# asam1_4.net
KiCad netlist of a schematic drawn in EAGLE
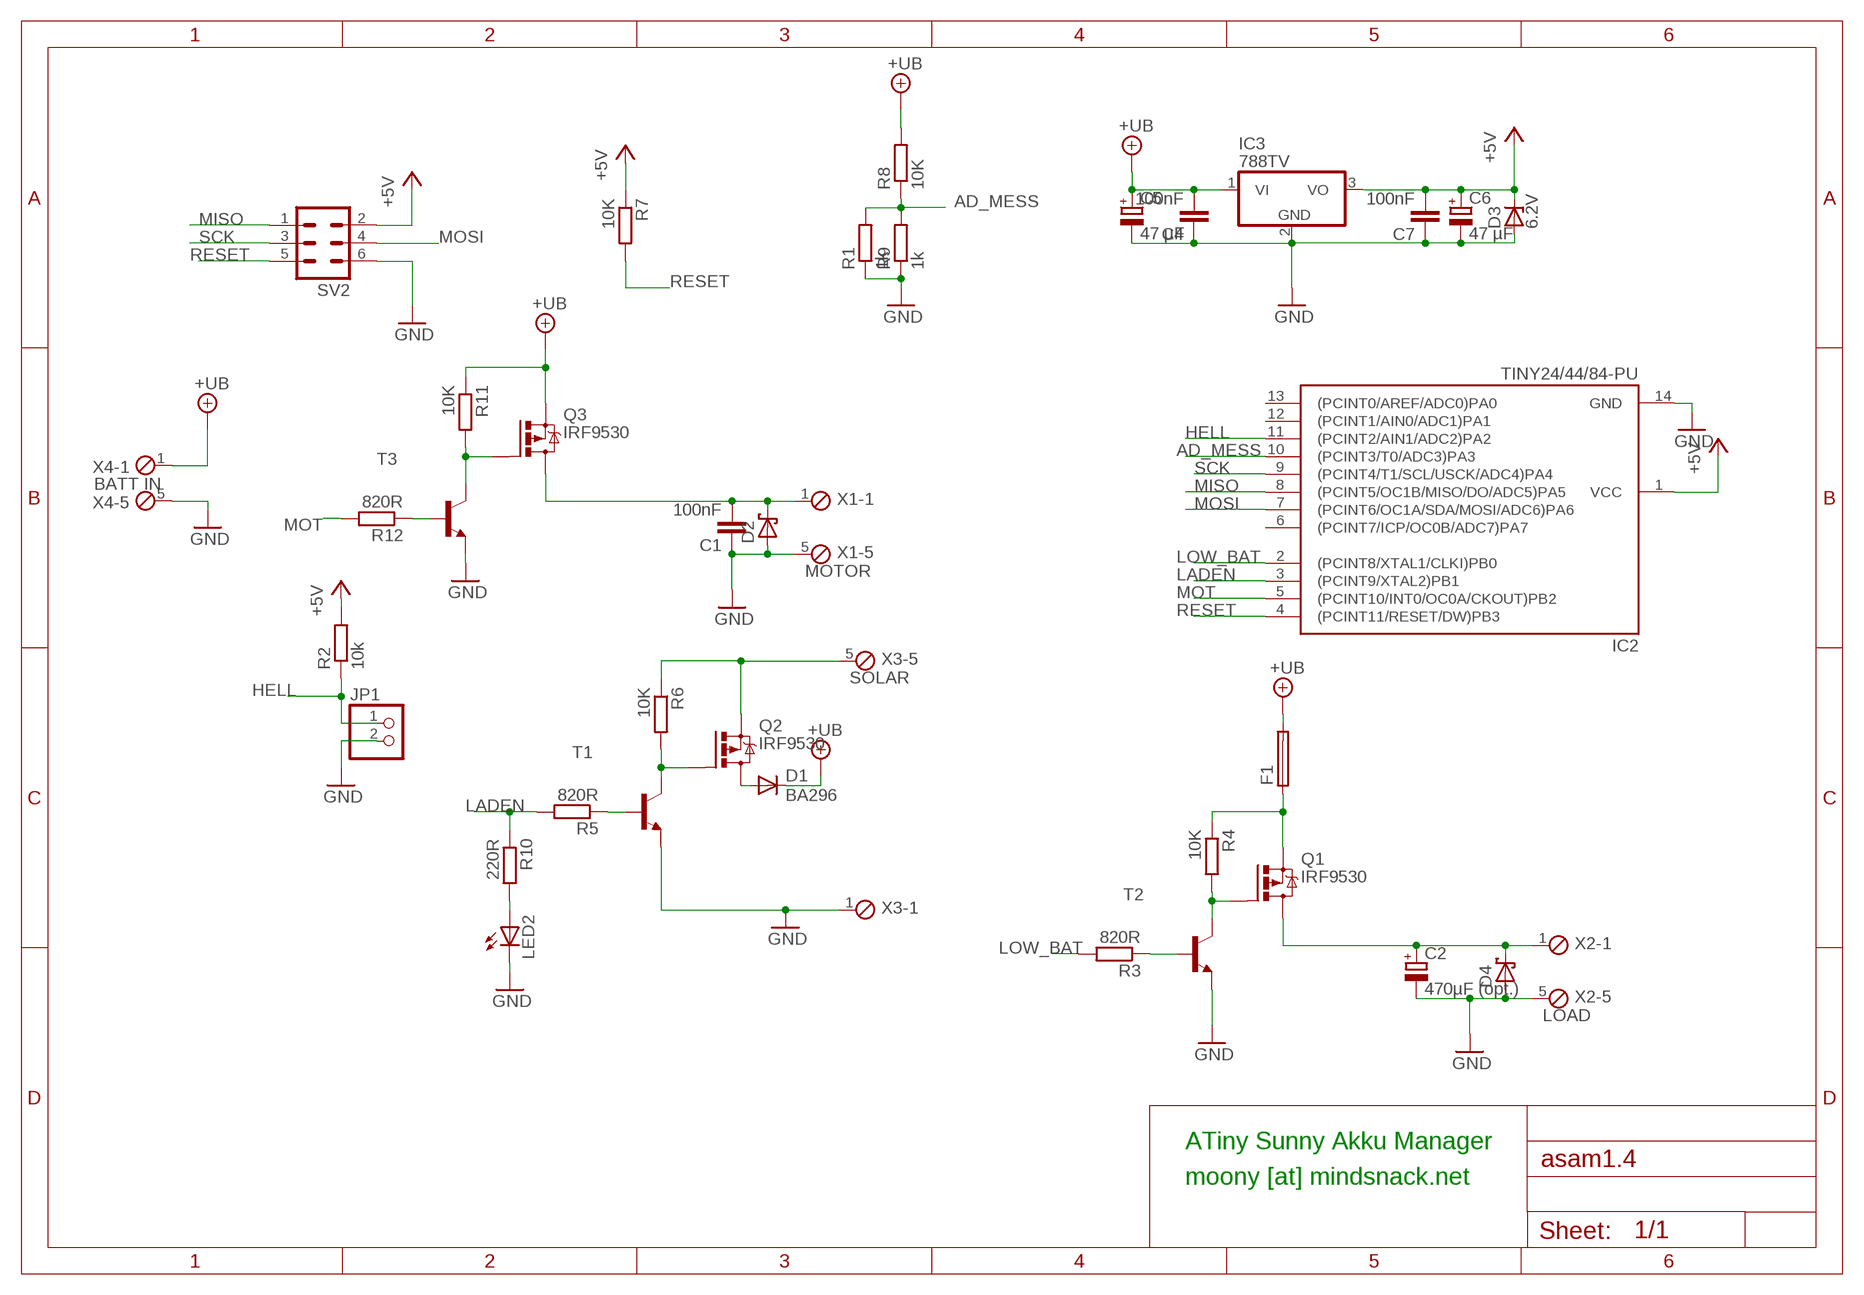
[diagram p0: schematic, sheet 1]

(export (version "E")
  (design (tool "Eeschema 10.0.6"))
  (components
    (comp (ref "C1")
      (value "100nF")
      (footprint "eagle-import:C075-032X103")
      (libsource (lib "eagle-import") (part "C-EU075-032X103"))
    )
    (comp (ref "C2")
      (value "470µF (opt.)")
      (footprint "eagle-import:E5-10,5")
      (libsource (lib "eagle-import") (part "CPOL-EUE5-10.5"))
    )
    (comp (ref "C4")
      (value "100nF")
      (footprint "eagle-import:C075-032X103")
      (libsource (lib "eagle-import") (part "C-EU075-032X103"))
    )
    (comp (ref "C5")
      (value "47 µF")
      (footprint "eagle-import:E5-10,5")
      (libsource (lib "eagle-import") (part "CPOL-EUE5-10.5"))
    )
    (comp (ref "C6")
      (value "47 µF")
      (footprint "eagle-import:E5-10,5")
      (libsource (lib "eagle-import") (part "CPOL-EUE5-10.5"))
    )
    (comp (ref "C7")
      (value "100nF")
      (footprint "eagle-import:C075-032X103")
      (libsource (lib "eagle-import") (part "C-EU075-032X103"))
    )
    (comp (ref "D1")
      (value "BA296")
      (footprint "eagle-import:P2-15")
      (libsource (lib "eagle-import") (part "BA296"))
    )
    (comp (ref "D2")
      (value "SCHOTTKY-DIODEDO35-7")
      (footprint "eagle-import:DO35-7")
      (libsource (lib "eagle-import") (part "SCHOTTKY-DIODEDO35-7"))
    )
    (comp (ref "D3")
      (value "6.2V")
      (footprint "eagle-import:C1702-15")
      (libsource (lib "eagle-import") (part "ZENER-DIODEC1702-15"))
    )
    (comp (ref "D4")
      (value "SCHOTTKY-DIODEDO35-7")
      (footprint "eagle-import:DO35-7")
      (libsource (lib "eagle-import") (part "SCHOTTKY-DIODEDO35-7"))
    )
    (comp (ref "F1")
      (value "SH22,5")
      (footprint "eagle-import:SH22,5")
      (fields (field (name "MF") "SCHURTER") (field (name "MPN") "0031.8201"))
      (libsource (lib "eagle-import") (part "SH22,5"))
    )
    (comp (ref "IC2")
      (value "TINY24/44/84-PU")
      (footprint "eagle-import:DIL14")
      (libsource (lib "eagle-import") (part "TINY24/44/84-PU"))
    )
    (comp (ref "IC3")
      (value "788TV")
      (footprint "eagle-import:TO220V")
      (libsource (lib "eagle-import") (part "78TV8"))
    )
    (comp (ref "JP1")
      (value "PINHD-1X2")
      (footprint "eagle-import:1X02")
      (libsource (lib "eagle-import") (part "PINHD-1X2"))
    )
    (comp (ref "LED2")
      (value "LED3MM")
      (footprint "eagle-import:LED3MM")
      (libsource (lib "eagle-import") (part "LED3MM"))
    )
    (comp (ref "Q1")
      (value "IRF9530")
      (footprint "eagle-import:TO220BV")
      (libsource (lib "eagle-import") (part "IRF9530"))
    )
    (comp (ref "Q2")
      (value "IRF9530")
      (footprint "eagle-import:TO220BV")
      (libsource (lib "eagle-import") (part "IRF9530"))
    )
    (comp (ref "Q3")
      (value "IRF9530")
      (footprint "eagle-import:TO220BV")
      (libsource (lib "eagle-import") (part "IRF9530"))
    )
    (comp (ref "R1")
      (value "1k")
      (footprint "eagle-import:0207_10")
      (libsource (lib "eagle-import") (part "R-EU_0207/10"))
    )
    (comp (ref "R2")
      (value "10k")
      (footprint "eagle-import:0207_10")
      (libsource (lib "eagle-import") (part "R-EU_0207/10"))
    )
    (comp (ref "R3")
      (value "820R")
      (footprint "eagle-import:0207_10")
      (libsource (lib "eagle-import") (part "R-EU_0207/10"))
    )
    (comp (ref "R4")
      (value "10K")
      (footprint "eagle-import:0207_12")
      (libsource (lib "eagle-import") (part "R-EU_0207/12"))
    )
    (comp (ref "R5")
      (value "820R")
      (footprint "eagle-import:0207_10")
      (libsource (lib "eagle-import") (part "R-EU_0207/10"))
    )
    (comp (ref "R6")
      (value "10K")
      (footprint "eagle-import:0207_12")
      (libsource (lib "eagle-import") (part "R-EU_0207/12"))
    )
    (comp (ref "R7")
      (value "10K")
      (footprint "eagle-import:0207_12")
      (libsource (lib "eagle-import") (part "R-EU_0207/12"))
    )
    (comp (ref "R8")
      (value "10K")
      (footprint "eagle-import:0207_10")
      (libsource (lib "eagle-import") (part "R-EU_0207/10"))
    )
    (comp (ref "R9")
      (value "1k")
      (footprint "eagle-import:0207_10")
      (libsource (lib "eagle-import") (part "R-EU_0207/10"))
    )
    (comp (ref "R10")
      (value "220R")
      (footprint "eagle-import:0207_10")
      (libsource (lib "eagle-import") (part "R-EU_0207/10"))
    )
    (comp (ref "R11")
      (value "10K")
      (footprint "eagle-import:0207_12")
      (libsource (lib "eagle-import") (part "R-EU_0207/12"))
    )
    (comp (ref "R12")
      (value "820R")
      (footprint "eagle-import:0207_10")
      (libsource (lib "eagle-import") (part "R-EU_0207/10"))
    )
    (comp (ref "SV2")
      (value "MA03-2")
      (footprint "eagle-import:MA03-2")
      (libsource (lib "eagle-import") (part "MA03-2"))
    )
    (comp (ref "T1")
      (value "BC546-NPN-TO92-CBE")
      (footprint "eagle-import:TO92-CBE")
      (libsource (lib "eagle-import") (part "-NPN-TO92-CBEBC546"))
    )
    (comp (ref "T2")
      (value "BC546-NPN-TO92-CBE")
      (footprint "eagle-import:TO92-CBE")
      (libsource (lib "eagle-import") (part "-NPN-TO92-CBEBC546"))
    )
    (comp (ref "T3")
      (value "BC546-NPN-TO92-CBE")
      (footprint "eagle-import:TO92-CBE")
      (libsource (lib "eagle-import") (part "-NPN-TO92-CBEBC546"))
    )
    (comp (ref "X1")
      (value "MOTOR")
      (footprint "eagle-import:5POL254")
      (libsource (lib "eagle-import") (part "MPT5"))
    )
    (comp (ref "X2")
      (value "LOAD")
      (footprint "eagle-import:5POL254")
      (libsource (lib "eagle-import") (part "MPT5"))
    )
    (comp (ref "X3")
      (value "SOLAR")
      (footprint "eagle-import:5POL254")
      (libsource (lib "eagle-import") (part "MPT5"))
    )
    (comp (ref "X4")
      (value "BATT IN")
      (footprint "eagle-import:5POL254")
      (libsource (lib "eagle-import") (part "MPT5"))
    )
  )
  (nets
    (net (code "1") (name "+5V") (class "Default")
      (node (ref "C6") (pin "+") (pinfunction "+_+") (pintype "passive"))
      (node (ref "C7") (pin "2") (pinfunction "2_2") (pintype "passive"))
      (node (ref "D3") (pin "C") (pinfunction "C_C") (pintype "passive"))
      (node (ref "IC2") (pin "1") (pinfunction "VCC_1") (pintype "power_in"))
      (node (ref "IC3") (pin "3") (pinfunction "VO_3") (pintype "passive"))
      (node (ref "R2") (pin "2") (pinfunction "2_2") (pintype "passive"))
      (node (ref "R7") (pin "1") (pinfunction "1_1") (pintype "passive"))
      (node (ref "SV2") (pin "2") (pinfunction "2_2") (pintype "passive"))
    )
    (net (code "2") (name "+UB") (class "Default")
      (node (ref "C4") (pin "2") (pinfunction "2_2") (pintype "passive"))
      (node (ref "C5") (pin "+") (pinfunction "+_+") (pintype "passive"))
      (node (ref "D1") (pin "C") (pinfunction "C_C") (pintype "passive"))
      (node (ref "F1") (pin "2") (pinfunction "2_2") (pintype "passive"))
      (node (ref "IC3") (pin "1") (pinfunction "VI_1") (pintype "input"))
      (node (ref "Q3") (pin "S") (pinfunction "S_S") (pintype "passive"))
      (node (ref "R11") (pin "1") (pinfunction "1_1") (pintype "passive"))
      (node (ref "R8") (pin "2") (pinfunction "2_2") (pintype "passive"))
      (node (ref "X4") (pin "1") (pinfunction "1_1") (pintype "passive"))
    )
    (net (code "3") (name "/AD_MESS") (class "Default")
      (node (ref "IC2") (pin "10") (pinfunction "(PCINT3/T0/ADC3)PA3_10") (pintype "bidirectional"))
      (node (ref "R1") (pin "2") (pinfunction "2_2") (pintype "passive"))
      (node (ref "R8") (pin "1") (pinfunction "1_1") (pintype "passive"))
      (node (ref "R9") (pin "2") (pinfunction "2_2") (pintype "passive"))
    )
    (net (code "4") (name "/HELL") (class "Default")
      (node (ref "IC2") (pin "11") (pinfunction "(PCINT2/AIN1/ADC2)PA2_11") (pintype "bidirectional"))
      (node (ref "JP1") (pin "1") (pinfunction "1_1") (pintype "passive"))
      (node (ref "R2") (pin "1") (pinfunction "1_1") (pintype "passive"))
    )
    (net (code "5") (name "/LADEN") (class "Default")
      (node (ref "IC2") (pin "3") (pinfunction "(PCINT9/XTAL2)PB1_3") (pintype "bidirectional"))
      (node (ref "R10") (pin "1") (pinfunction "1_1") (pintype "passive"))
      (node (ref "R5") (pin "2") (pinfunction "2_2") (pintype "passive"))
    )
    (net (code "6") (name "/LOW_BAT") (class "Default")
      (node (ref "IC2") (pin "2") (pinfunction "(PCINT8/XTAL1/CLKI)PB0_2") (pintype "bidirectional"))
      (node (ref "R3") (pin "2") (pinfunction "2_2") (pintype "passive"))
    )
    (net (code "7") (name "/MISO") (class "Default")
      (node (ref "IC2") (pin "8") (pinfunction "(PCINT5/OC1B/MISO/DO/ADC5)PA5_8") (pintype "bidirectional"))
      (node (ref "SV2") (pin "1") (pinfunction "1_1") (pintype "passive"))
    )
    (net (code "8") (name "/MOSI") (class "Default")
      (node (ref "IC2") (pin "7") (pinfunction "(PCINT6/OC1A/SDA/MOSI/ADC6)PA6_7") (pintype "bidirectional"))
      (node (ref "SV2") (pin "4") (pinfunction "4_4") (pintype "passive"))
    )
    (net (code "9") (name "/MOT") (class "Default")
      (node (ref "IC2") (pin "5") (pinfunction "(PCINT10/INT0/OC0A/CKOUT)PB2_5") (pintype "bidirectional"))
      (node (ref "R12") (pin "2") (pinfunction "2_2") (pintype "passive"))
    )
    (net (code "10") (name "/RESET") (class "Default")
      (node (ref "IC2") (pin "4") (pinfunction "(PCINT11/RESET/DW)PB3_4") (pintype "bidirectional"))
      (node (ref "R7") (pin "2") (pinfunction "2_2") (pintype "passive"))
      (node (ref "SV2") (pin "5") (pinfunction "5_5") (pintype "passive"))
    )
    (net (code "11") (name "/SCK") (class "Default")
      (node (ref "IC2") (pin "9") (pinfunction "(PCINT4/T1/SCL/USCK/ADC4)PA4_9") (pintype "bidirectional"))
      (node (ref "SV2") (pin "3") (pinfunction "3_3") (pintype "passive"))
    )
    (net (code "12") (name "GND") (class "Default")
      (node (ref "C1") (pin "1") (pinfunction "1_1") (pintype "passive"))
      (node (ref "C2") (pin "-") (pinfunction "-_-") (pintype "passive"))
      (node (ref "C4") (pin "1") (pinfunction "1_1") (pintype "passive"))
      (node (ref "C5") (pin "-") (pinfunction "-_-") (pintype "passive"))
      (node (ref "C6") (pin "-") (pinfunction "-_-") (pintype "passive"))
      (node (ref "C7") (pin "1") (pinfunction "1_1") (pintype "passive"))
      (node (ref "D2") (pin "A") (pinfunction "A_A") (pintype "passive"))
      (node (ref "D3") (pin "A") (pinfunction "A_A") (pintype "passive"))
      (node (ref "D4") (pin "A") (pinfunction "A_A") (pintype "passive"))
      (node (ref "IC2") (pin "14") (pinfunction "GND_14") (pintype "power_in"))
      (node (ref "IC3") (pin "2") (pinfunction "GND_2") (pintype "passive"))
      (node (ref "JP1") (pin "2") (pinfunction "2_2") (pintype "passive"))
      (node (ref "LED2") (pin "K") (pinfunction "C_K") (pintype "passive"))
      (node (ref "R1") (pin "1") (pinfunction "1_1") (pintype "passive"))
      (node (ref "R9") (pin "1") (pinfunction "1_1") (pintype "passive"))
      (node (ref "SV2") (pin "6") (pinfunction "6_6") (pintype "passive"))
      (node (ref "T1") (pin "E") (pinfunction "E_E") (pintype "passive"))
      (node (ref "T2") (pin "E") (pinfunction "E_E") (pintype "passive"))
      (node (ref "T3") (pin "E") (pinfunction "E_E") (pintype "passive"))
      (node (ref "X1") (pin "5") (pinfunction "1_5") (pintype "passive"))
      (node (ref "X2") (pin "5") (pinfunction "1_5") (pintype "passive"))
      (node (ref "X3") (pin "1") (pinfunction "1_1") (pintype "passive"))
      (node (ref "X4") (pin "5") (pinfunction "1_5") (pintype "passive"))
    )
    (net (code "13") (name "Net-(C1-Pad2)") (class "Default")
      (node (ref "C1") (pin "2") (pinfunction "2_2") (pintype "passive"))
      (node (ref "D2") (pin "C") (pinfunction "C_C") (pintype "passive"))
      (node (ref "Q3") (pin "D") (pinfunction "D_D") (pintype "passive"))
      (node (ref "X1") (pin "1") (pinfunction "1_1") (pintype "passive"))
    )
    (net (code "14") (name "Net-(C2-Pad+)") (class "Default")
      (node (ref "C2") (pin "+") (pinfunction "+_+") (pintype "passive"))
      (node (ref "D4") (pin "C") (pinfunction "C_C") (pintype "passive"))
      (node (ref "Q1") (pin "D") (pinfunction "D_D") (pintype "passive"))
      (node (ref "X2") (pin "1") (pinfunction "1_1") (pintype "passive"))
    )
    (net (code "15") (name "Net-(D1-PadA)") (class "Default")
      (node (ref "D1") (pin "A") (pinfunction "A_A") (pintype "passive"))
      (node (ref "Q2") (pin "D") (pinfunction "D_D") (pintype "passive"))
    )
    (net (code "16") (name "Net-(F1-Pad1)") (class "Default")
      (node (ref "F1") (pin "1") (pinfunction "1_1") (pintype "passive"))
      (node (ref "Q1") (pin "S") (pinfunction "S_S") (pintype "passive"))
      (node (ref "R4") (pin "1") (pinfunction "1_1") (pintype "passive"))
    )
    (net (code "17") (name "Net-(LED2-PadA)") (class "Default")
      (node (ref "LED2") (pin "A") (pinfunction "A_A") (pintype "passive"))
      (node (ref "R10") (pin "2") (pinfunction "2_2") (pintype "passive"))
    )
    (net (code "18") (name "Net-(Q1-PadG)") (class "Default")
      (node (ref "Q1") (pin "G") (pinfunction "G_G") (pintype "passive"))
      (node (ref "R4") (pin "2") (pinfunction "2_2") (pintype "passive"))
      (node (ref "T2") (pin "C") (pinfunction "C_C") (pintype "passive"))
    )
    (net (code "19") (name "Net-(Q2-PadG)") (class "Default")
      (node (ref "Q2") (pin "G") (pinfunction "G_G") (pintype "passive"))
      (node (ref "R6") (pin "2") (pinfunction "2_2") (pintype "passive"))
      (node (ref "T1") (pin "C") (pinfunction "C_C") (pintype "passive"))
    )
    (net (code "20") (name "Net-(Q3-PadG)") (class "Default")
      (node (ref "Q3") (pin "G") (pinfunction "G_G") (pintype "passive"))
      (node (ref "R11") (pin "2") (pinfunction "2_2") (pintype "passive"))
      (node (ref "T3") (pin "C") (pinfunction "C_C") (pintype "passive"))
    )
    (net (code "21") (name "Net-(R3-Pad1)") (class "Default")
      (node (ref "R3") (pin "1") (pinfunction "1_1") (pintype "passive"))
      (node (ref "T2") (pin "B") (pinfunction "B_B") (pintype "passive"))
    )
    (net (code "22") (name "Net-(R5-Pad1)") (class "Default")
      (node (ref "R5") (pin "1") (pinfunction "1_1") (pintype "passive"))
      (node (ref "T1") (pin "B") (pinfunction "B_B") (pintype "passive"))
    )
    (net (code "23") (name "Net-(R12-Pad1)") (class "Default")
      (node (ref "R12") (pin "1") (pinfunction "1_1") (pintype "passive"))
      (node (ref "T3") (pin "B") (pinfunction "B_B") (pintype "passive"))
    )
    (net (code "24") (name "Net-(X3E-1)") (class "Default")
      (node (ref "Q2") (pin "S") (pinfunction "S_S") (pintype "passive"))
      (node (ref "R6") (pin "1") (pinfunction "1_1") (pintype "passive"))
      (node (ref "X3") (pin "5") (pinfunction "1_5") (pintype "passive"))
    )
    (net (code "25") (name "unconnected-(IC2-(PCINT0{slash}AREF{slash}ADC0)PA0-Pad13)") (class "Default")
      (node (ref "IC2") (pin "13") (pinfunction "(PCINT0/AREF/ADC0)PA0_13") (pintype "bidirectional"))
    )
    (net (code "26") (name "unconnected-(IC2-(PCINT1{slash}AIN0{slash}ADC1)PA1-Pad12)") (class "Default")
      (node (ref "IC2") (pin "12") (pinfunction "(PCINT1/AIN0/ADC1)PA1_12") (pintype "bidirectional"))
    )
    (net (code "27") (name "unconnected-(IC2-(PCINT7{slash}ICP{slash}OC0B{slash}ADC7)PA7-Pad6)") (class "Default")
      (node (ref "IC2") (pin "6") (pinfunction "(PCINT7/ICP/OC0B/ADC7)PA7_6") (pintype "bidirectional"))
    )
  )
)
